# usb.net
KiCad netlist of a schematic drawn in Altium Designer
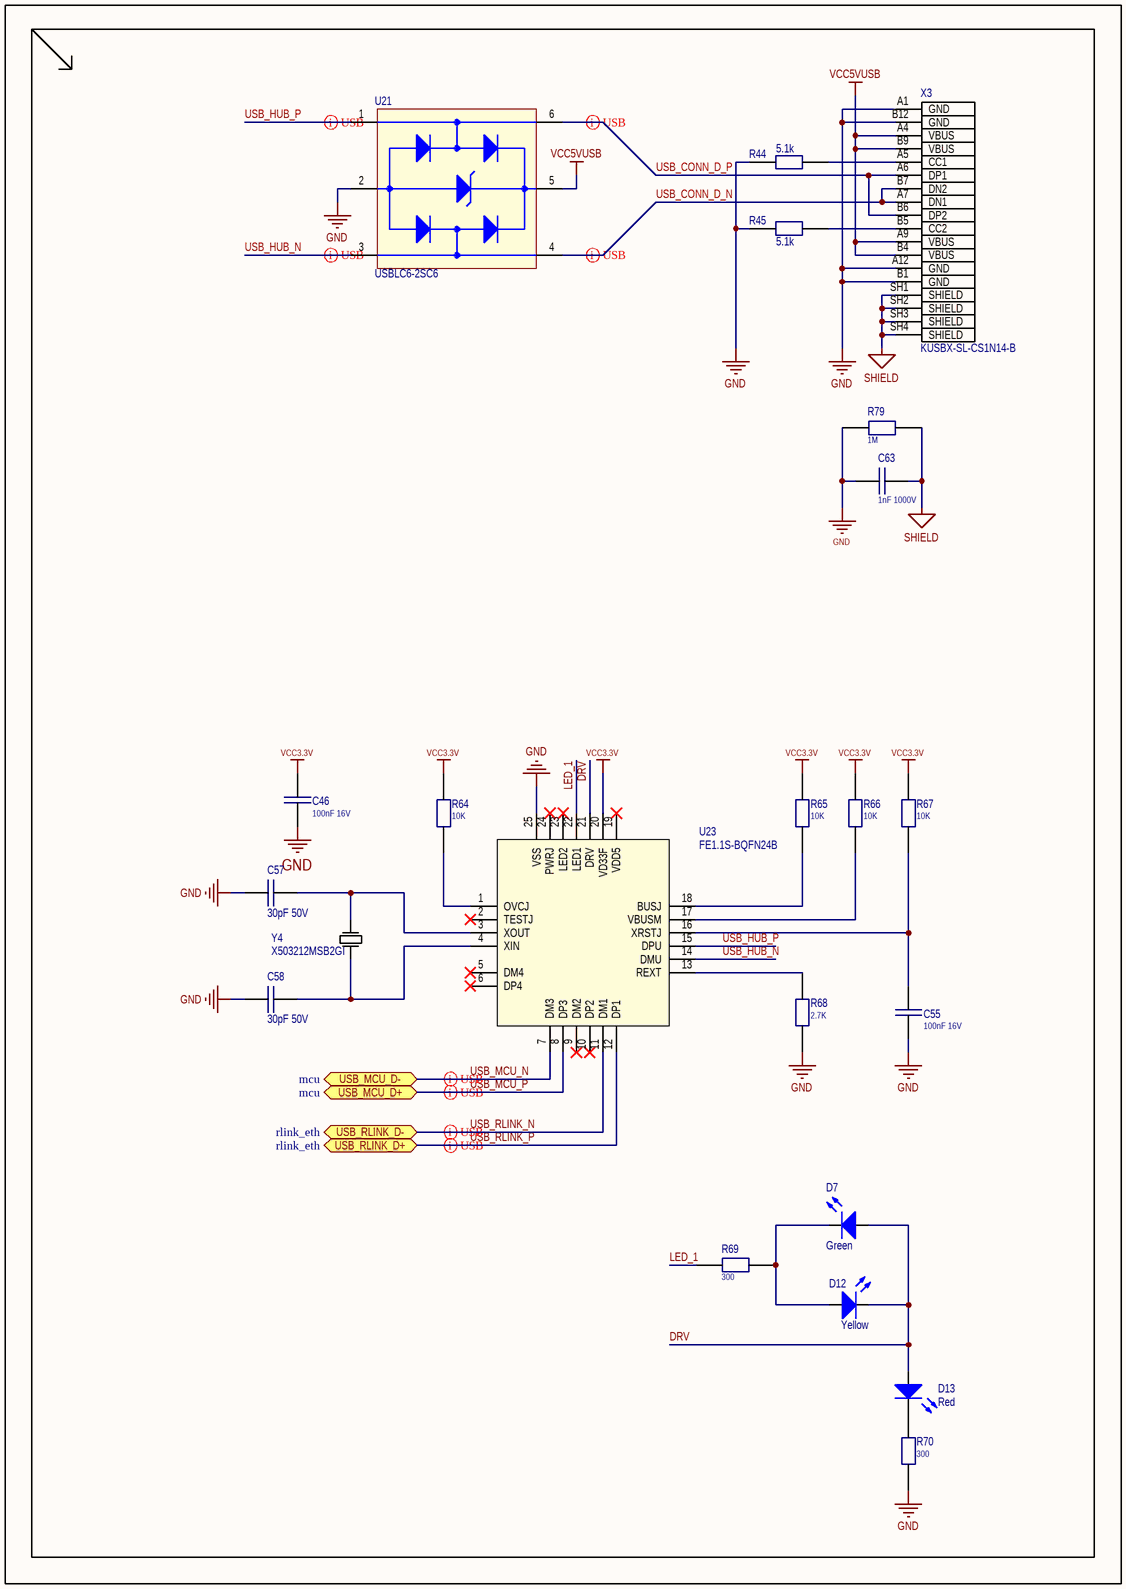
[diagram p0: usb.SchDoc]

(export (version "E")
  (design (tool "Eeschema 10.0.6"))
  (components
    (comp (ref "C46")
      (value "100nF 16V")
      (footprint "C_0402")
      (description "Capacitor")
      (fields (field (name "PART") "CC0402KRX7R7BB104") (field (name "ALTERNATIVE PART") "CC0402KRX5R7BB104"))
      (libsource (lib "capacitors") (part "C0402"))
    )
    (comp (ref "C55")
      (value "100nF 16V")
      (footprint "C_0402")
      (description "Capacitor")
      (fields (field (name "PART") "CC0402KRX7R7BB104") (field (name "ALTERNATIVE PART") "CC0402KRX5R7BB104"))
      (libsource (lib "capacitors") (part "C0402"))
    )
    (comp (ref "C57")
      (value "30pF 50V")
      (footprint "C_0603")
      (description "Capacitor")
      (fields (field (name "PART") "CC0603JRNPO9BN300"))
      (libsource (lib "capacitors") (part "CAP_SMD"))
    )
    (comp (ref "C58")
      (value "30pF 50V")
      (footprint "C_0603")
      (description "Capacitor")
      (fields (field (name "PART") "CC0603JRNPO9BN300"))
      (libsource (lib "capacitors") (part "CAP_SMD"))
    )
    (comp (ref "C63")
      (value "1nF 1000V")
      (footprint "C_1206")
      (description "Capacitor")
      (fields (field (name "PART") "CC1206KKX7RCBB102") (field (name "ALTERNATIVE PART") "CL31B102KIFNNNE"))
      (libsource (lib "capacitors") (part "C1206"))
    )
    (comp (ref "D7")
      (value "Green")
      (footprint "LED_0603")
      (description "LED")
      (fields (field (name "PART") "FYLS-0603PGC") (field (name "ALTERNATIVE PART") "KP-1608CGCK"))
      (libsource (lib "led_lcd") (part "LED_SMT_0603"))
    )
    (comp (ref "D12")
      (value "Yellow")
      (footprint "LED_0603")
      (description "LED")
      (fields (field (name "PART") "FYLS-0603PGC") (field (name "ALTERNATIVE PART") "KP-1608CGCK"))
      (libsource (lib "led_lcd") (part "LED_SMT_0603"))
    )
    (comp (ref "D13")
      (value "Red")
      (footprint "LED_0603")
      (description "LED")
      (fields (field (name "PART") "FYLS-0603PGC") (field (name "ALTERNATIVE PART") "KP-1608CGCK"))
      (libsource (lib "led_lcd") (part "LED_SMT_0603"))
    )
    (comp (ref "R44")
      (value "5.1k")
      (footprint "R_0603")
      (description "Resistor")
      (fields (field (name "PART") "RC0603JR-075K1L"))
      (libsource (lib "resistors") (part "RES_SMD"))
    )
    (comp (ref "R45")
      (value "5.1k")
      (footprint "R_0603")
      (description "Resistor")
      (fields (field (name "PART") "RC0603JR-075K1L"))
      (libsource (lib "resistors") (part "RES_SMD"))
    )
    (comp (ref "R64")
      (value "10K")
      (footprint "R_0402")
      (description "Resistor")
      (fields (field (name "PART") "RC0402JR-0710KL"))
      (libsource (lib "resistors") (part "R0402"))
    )
    (comp (ref "R65")
      (value "10K")
      (footprint "R_0402")
      (description "Resistor")
      (fields (field (name "PART") "RC0402JR-0710KL"))
      (libsource (lib "resistors") (part "R0402"))
    )
    (comp (ref "R66")
      (value "10K")
      (footprint "R_0402")
      (description "Resistor")
      (fields (field (name "PART") "RC0402JR-0710KL"))
      (libsource (lib "resistors") (part "R0402"))
    )
    (comp (ref "R67")
      (value "10K")
      (footprint "R_0402")
      (description "Resistor")
      (fields (field (name "PART") "RC0402JR-0710KL"))
      (libsource (lib "resistors") (part "R0402"))
    )
    (comp (ref "R68")
      (value "2.7K")
      (footprint "R_0402")
      (description "Resistor")
      (fields (field (name "PART") "RC0402FR-072K7L"))
      (libsource (lib "resistors") (part "R0402"))
    )
    (comp (ref "R69")
      (value "300")
      (footprint "R_0603")
      (description "Resistor")
      (fields (field (name "PART") "RC0603FR-07300RL"))
      (libsource (lib "resistors") (part "R0603"))
    )
    (comp (ref "R70")
      (value "300")
      (footprint "R_0603")
      (description "Resistor")
      (fields (field (name "PART") "RC0603FR-07300RL"))
      (libsource (lib "resistors") (part "R0603"))
    )
    (comp (ref "R79")
      (value "1M")
      (footprint "R_1206")
      (description "Resistor")
      (fields (field (name "PART") "RC1206FR-071ML"))
      (libsource (lib "resistors") (part "R1206"))
    )
    (comp (ref "U21")
      (value "USBLC6-2SC6")
      (footprint "diode:SOT95P280X145-6N")
      (description "17V Clamp 5A (8/20Âµs) Ipp Tvs Diode Surface Mount SOT-23-6")
      (fields (field (name "MF") "STMicroelectronics"))
      (libsource (lib "diode") (part "USBLC6-2SC6"))
    )
    (comp (ref "U23")
      (value "FE1.1S-BQFN24B")
      (footprint "QFN50P400X400X80-25N-D")
      (description "USB 2.0 HIGH SPEED 4-PORT HUB CONTROLLER")
      (libsource (lib "discret_ic") (part "FE1.1S-BQFN24B"))
    )
    (comp (ref "X3")
      (value "KUSBX-SL-CS1N14-B")
      (footprint "MOLEX_2169890001")
      (description "USB Connector USB TYPE C UPRIGHT STRAIGHT TAB 14 PIN")
      (libsource (lib "connectors_socets") (part "MOLEX_216989-0001"))
    )
    (comp (ref "Y4")
      (value "X503212MSB2GI")
      (footprint "X5032")
      (description "Crystal Oscillator")
      (libsource (lib "crystals_oscillators") (part "X503212MSB2GI"))
    )
  )
  (nets
    (net (code "1") (name "/DRV") (class "Default")
      (node (ref "D12") (pin "2") (pinfunction "K_2") (pintype "passive"))
      (node (ref "D13") (pin "1") (pinfunction "A_1") (pintype "passive"))
      (node (ref "D7") (pin "1") (pinfunction "A_1") (pintype "passive"))
      (node (ref "U23") (pin "21") (pinfunction "DRV_21") (pintype "passive"))
    )
    (net (code "2") (name "/LED_1") (class "Default")
      (node (ref "R69") (pin "2") (pinfunction "2_2") (pintype "passive"))
      (node (ref "U23") (pin "22") (pinfunction "LED1_22") (pintype "passive"))
    )
    (net (code "3") (name "/USB_CONN_D_N") (class "Default")
      (node (ref "U21") (pin "4") (pinfunction "I/O2_OUT_4") (pintype "passive"))
      (node (ref "X3") (pin "A7") (pinfunction "DN1_A7") (pintype "passive"))
      (node (ref "X3") (pin "B7") (pinfunction "DN2_B7") (pintype "passive"))
    )
    (net (code "4") (name "/USB_CONN_D_P") (class "Default")
      (node (ref "U21") (pin "6") (pinfunction "I/O1_OUT_6") (pintype "passive"))
      (node (ref "X3") (pin "A6") (pinfunction "DP1_A6") (pintype "passive"))
      (node (ref "X3") (pin "B6") (pinfunction "DP2_B6") (pintype "passive"))
    )
    (net (code "5") (name "/USB_HUB_N") (class "Default")
      (node (ref "U21") (pin "3") (pinfunction "I/O2_IN_3") (pintype "passive"))
      (node (ref "U23") (pin "14") (pinfunction "DMU_14") (pintype "passive"))
    )
    (net (code "6") (name "/USB_HUB_P") (class "Default")
      (node (ref "U21") (pin "1") (pinfunction "I/O1_IN_1") (pintype "passive"))
      (node (ref "U23") (pin "15") (pinfunction "DPU_15") (pintype "passive"))
    )
    (net (code "7") (name "/USB_MCU_N") (class "Default")
      (node (ref "U23") (pin "7") (pinfunction "DM3_7") (pintype "passive"))
    )
    (net (code "8") (name "/USB_MCU_P") (class "Default")
      (node (ref "U23") (pin "8") (pinfunction "DP3_8") (pintype "passive"))
    )
    (net (code "9") (name "/USB_RLINK_N") (class "Default")
      (node (ref "U23") (pin "11") (pinfunction "DM1_11") (pintype "passive"))
    )
    (net (code "10") (name "/USB_RLINK_P") (class "Default")
      (node (ref "U23") (pin "12") (pinfunction "DP1_12") (pintype "passive"))
    )
    (net (code "11") (name "GND") (class "Default")
      (node (ref "C46") (pin "1") (pinfunction "1_1") (pintype "passive"))
      (node (ref "C55") (pin "2") (pinfunction "2_2") (pintype "passive"))
      (node (ref "C57") (pin "2") (pinfunction "2_2") (pintype "passive"))
      (node (ref "C58") (pin "2") (pinfunction "2_2") (pintype "passive"))
      (node (ref "C63") (pin "1") (pinfunction "1_1") (pintype "passive"))
      (node (ref "R44") (pin "1") (pinfunction "1_1") (pintype "passive"))
      (node (ref "R45") (pin "1") (pinfunction "1_1") (pintype "passive"))
      (node (ref "R68") (pin "2") (pinfunction "2_2") (pintype "passive"))
      (node (ref "R70") (pin "1") (pinfunction "1_1") (pintype "passive"))
      (node (ref "R79") (pin "1") (pinfunction "1_1") (pintype "passive"))
      (node (ref "U21") (pin "2") (pinfunction "GND_2") (pintype "passive"))
      (node (ref "U23") (pin "25") (pinfunction "VSS_25") (pintype "power_in"))
      (node (ref "X3") (pin "A1") (pinfunction "GND_A1") (pintype "passive"))
      (node (ref "X3") (pin "A12") (pinfunction "GND_A12") (pintype "passive"))
      (node (ref "X3") (pin "B1") (pinfunction "GND_B1") (pintype "passive"))
      (node (ref "X3") (pin "B12") (pinfunction "GND_B12") (pintype "passive"))
    )
    (net (code "12") (name "Net-(D12-A)") (class "Default")
      (node (ref "D12") (pin "1") (pinfunction "A_1") (pintype "passive"))
      (node (ref "D7") (pin "2") (pinfunction "K_2") (pintype "passive"))
      (node (ref "R69") (pin "1") (pinfunction "1_1") (pintype "passive"))
    )
    (net (code "13") (name "Net-(D13-K)") (class "Default")
      (node (ref "D13") (pin "2") (pinfunction "K_2") (pintype "passive"))
      (node (ref "R70") (pin "2") (pinfunction "2_2") (pintype "passive"))
    )
    (net (code "14") (name "Net-(U23-BUSJ)") (class "Default")
      (node (ref "R65") (pin "1") (pinfunction "1_1") (pintype "passive"))
      (node (ref "U23") (pin "18") (pinfunction "BUSJ_18") (pintype "passive"))
    )
    (net (code "15") (name "Net-(U23-OVCJ)") (class "Default")
      (node (ref "R64") (pin "1") (pinfunction "1_1") (pintype "passive"))
      (node (ref "U23") (pin "1") (pinfunction "OVCJ_1") (pintype "passive"))
    )
    (net (code "16") (name "Net-(U23-REXT)") (class "Default")
      (node (ref "R68") (pin "1") (pinfunction "1_1") (pintype "passive"))
      (node (ref "U23") (pin "13") (pinfunction "REXT_13") (pintype "passive"))
    )
    (net (code "17") (name "Net-(U23-VBUSM)") (class "Default")
      (node (ref "R66") (pin "1") (pinfunction "1_1") (pintype "passive"))
      (node (ref "U23") (pin "17") (pinfunction "VBUSM_17") (pintype "passive"))
    )
    (net (code "18") (name "Net-(U23-XIN)") (class "Default")
      (node (ref "C58") (pin "1") (pinfunction "1_1") (pintype "passive"))
      (node (ref "U23") (pin "4") (pinfunction "XIN_4") (pintype "passive"))
      (node (ref "Y4") (pin "2") (pinfunction "2_2") (pintype "passive"))
    )
    (net (code "19") (name "Net-(U23-XOUT)") (class "Default")
      (node (ref "C57") (pin "1") (pinfunction "1_1") (pintype "passive"))
      (node (ref "U23") (pin "3") (pinfunction "XOUT_3") (pintype "passive"))
      (node (ref "Y4") (pin "1") (pinfunction "1_1") (pintype "passive"))
    )
    (net (code "20") (name "Net-(U23-XRSTJ)") (class "Default")
      (node (ref "C55") (pin "1") (pinfunction "1_1") (pintype "passive"))
      (node (ref "R67") (pin "1") (pinfunction "1_1") (pintype "passive"))
      (node (ref "U23") (pin "16") (pinfunction "XRSTJ_16") (pintype "passive"))
    )
    (net (code "21") (name "Net-(X3-CC1)") (class "Default")
      (node (ref "R44") (pin "2") (pinfunction "2_2") (pintype "passive"))
      (node (ref "X3") (pin "A5") (pinfunction "CC1_A5") (pintype "passive"))
    )
    (net (code "22") (name "Net-(X3-CC2)") (class "Default")
      (node (ref "R45") (pin "2") (pinfunction "2_2") (pintype "passive"))
      (node (ref "X3") (pin "B5") (pinfunction "CC2_B5") (pintype "passive"))
    )
    (net (code "23") (name "SHIELD") (class "Default")
      (node (ref "C63") (pin "2") (pinfunction "2_2") (pintype "passive"))
      (node (ref "R79") (pin "2") (pinfunction "2_2") (pintype "passive"))
      (node (ref "X3") (pin "SH1") (pinfunction "SHIELD_SH1") (pintype "passive"))
      (node (ref "X3") (pin "SH2") (pinfunction "SHIELD_SH2") (pintype "passive"))
      (node (ref "X3") (pin "SH3") (pinfunction "SHIELD_SH3") (pintype "passive"))
      (node (ref "X3") (pin "SH4") (pinfunction "SHIELD_SH4") (pintype "passive"))
    )
    (net (code "24") (name "VCC3.3V") (class "Default")
      (node (ref "C46") (pin "2") (pinfunction "2_2") (pintype "passive"))
      (node (ref "R64") (pin "2") (pinfunction "2_2") (pintype "passive"))
      (node (ref "R65") (pin "2") (pinfunction "2_2") (pintype "passive"))
      (node (ref "R66") (pin "2") (pinfunction "2_2") (pintype "passive"))
      (node (ref "R67") (pin "2") (pinfunction "2_2") (pintype "passive"))
      (node (ref "U23") (pin "20") (pinfunction "VD33F_20") (pintype "power_in"))
    )
    (net (code "25") (name "VCC5VUSB") (class "Default")
      (node (ref "U21") (pin "5") (pinfunction "VBUS_5") (pintype "passive"))
      (node (ref "X3") (pin "A4") (pinfunction "VBUS_A4") (pintype "passive"))
      (node (ref "X3") (pin "A9") (pinfunction "VBUS_A9") (pintype "passive"))
      (node (ref "X3") (pin "B4") (pinfunction "VBUS_B4") (pintype "passive"))
      (node (ref "X3") (pin "B9") (pinfunction "VBUS_B9") (pintype "passive"))
    )
    (net (code "26") (name "unconnected-(U23-DM2-Pad9)") (class "Default")
      (node (ref "U23") (pin "9") (pinfunction "DM2_9") (pintype "passive+no_connect"))
    )
    (net (code "27") (name "unconnected-(U23-DM4-Pad5)") (class "Default")
      (node (ref "U23") (pin "5") (pinfunction "DM4_5") (pintype "passive+no_connect"))
    )
    (net (code "28") (name "unconnected-(U23-DP2-Pad10)") (class "Default")
      (node (ref "U23") (pin "10") (pinfunction "DP2_10") (pintype "passive+no_connect"))
    )
    (net (code "29") (name "unconnected-(U23-DP4-Pad6)") (class "Default")
      (node (ref "U23") (pin "6") (pinfunction "DP4_6") (pintype "passive+no_connect"))
    )
    (net (code "30") (name "unconnected-(U23-LED2-Pad23)") (class "Default")
      (node (ref "U23") (pin "23") (pinfunction "LED2_23") (pintype "passive+no_connect"))
    )
    (net (code "31") (name "unconnected-(U23-PWRJ-Pad24)") (class "Default")
      (node (ref "U23") (pin "24") (pinfunction "PWRJ_24") (pintype "passive+no_connect"))
    )
    (net (code "32") (name "unconnected-(U23-TESTJ-Pad2)") (class "Default")
      (node (ref "U23") (pin "2") (pinfunction "TESTJ_2") (pintype "passive+no_connect"))
    )
    (net (code "33") (name "unconnected-(U23-VDD5-Pad19)") (class "Default")
      (node (ref "U23") (pin "19") (pinfunction "VDD5_19") (pintype "power_in+no_connect"))
    )
  )
)
